# Schematic_STM32.net
KiCad netlist of a schematic drawn in Altium Designer
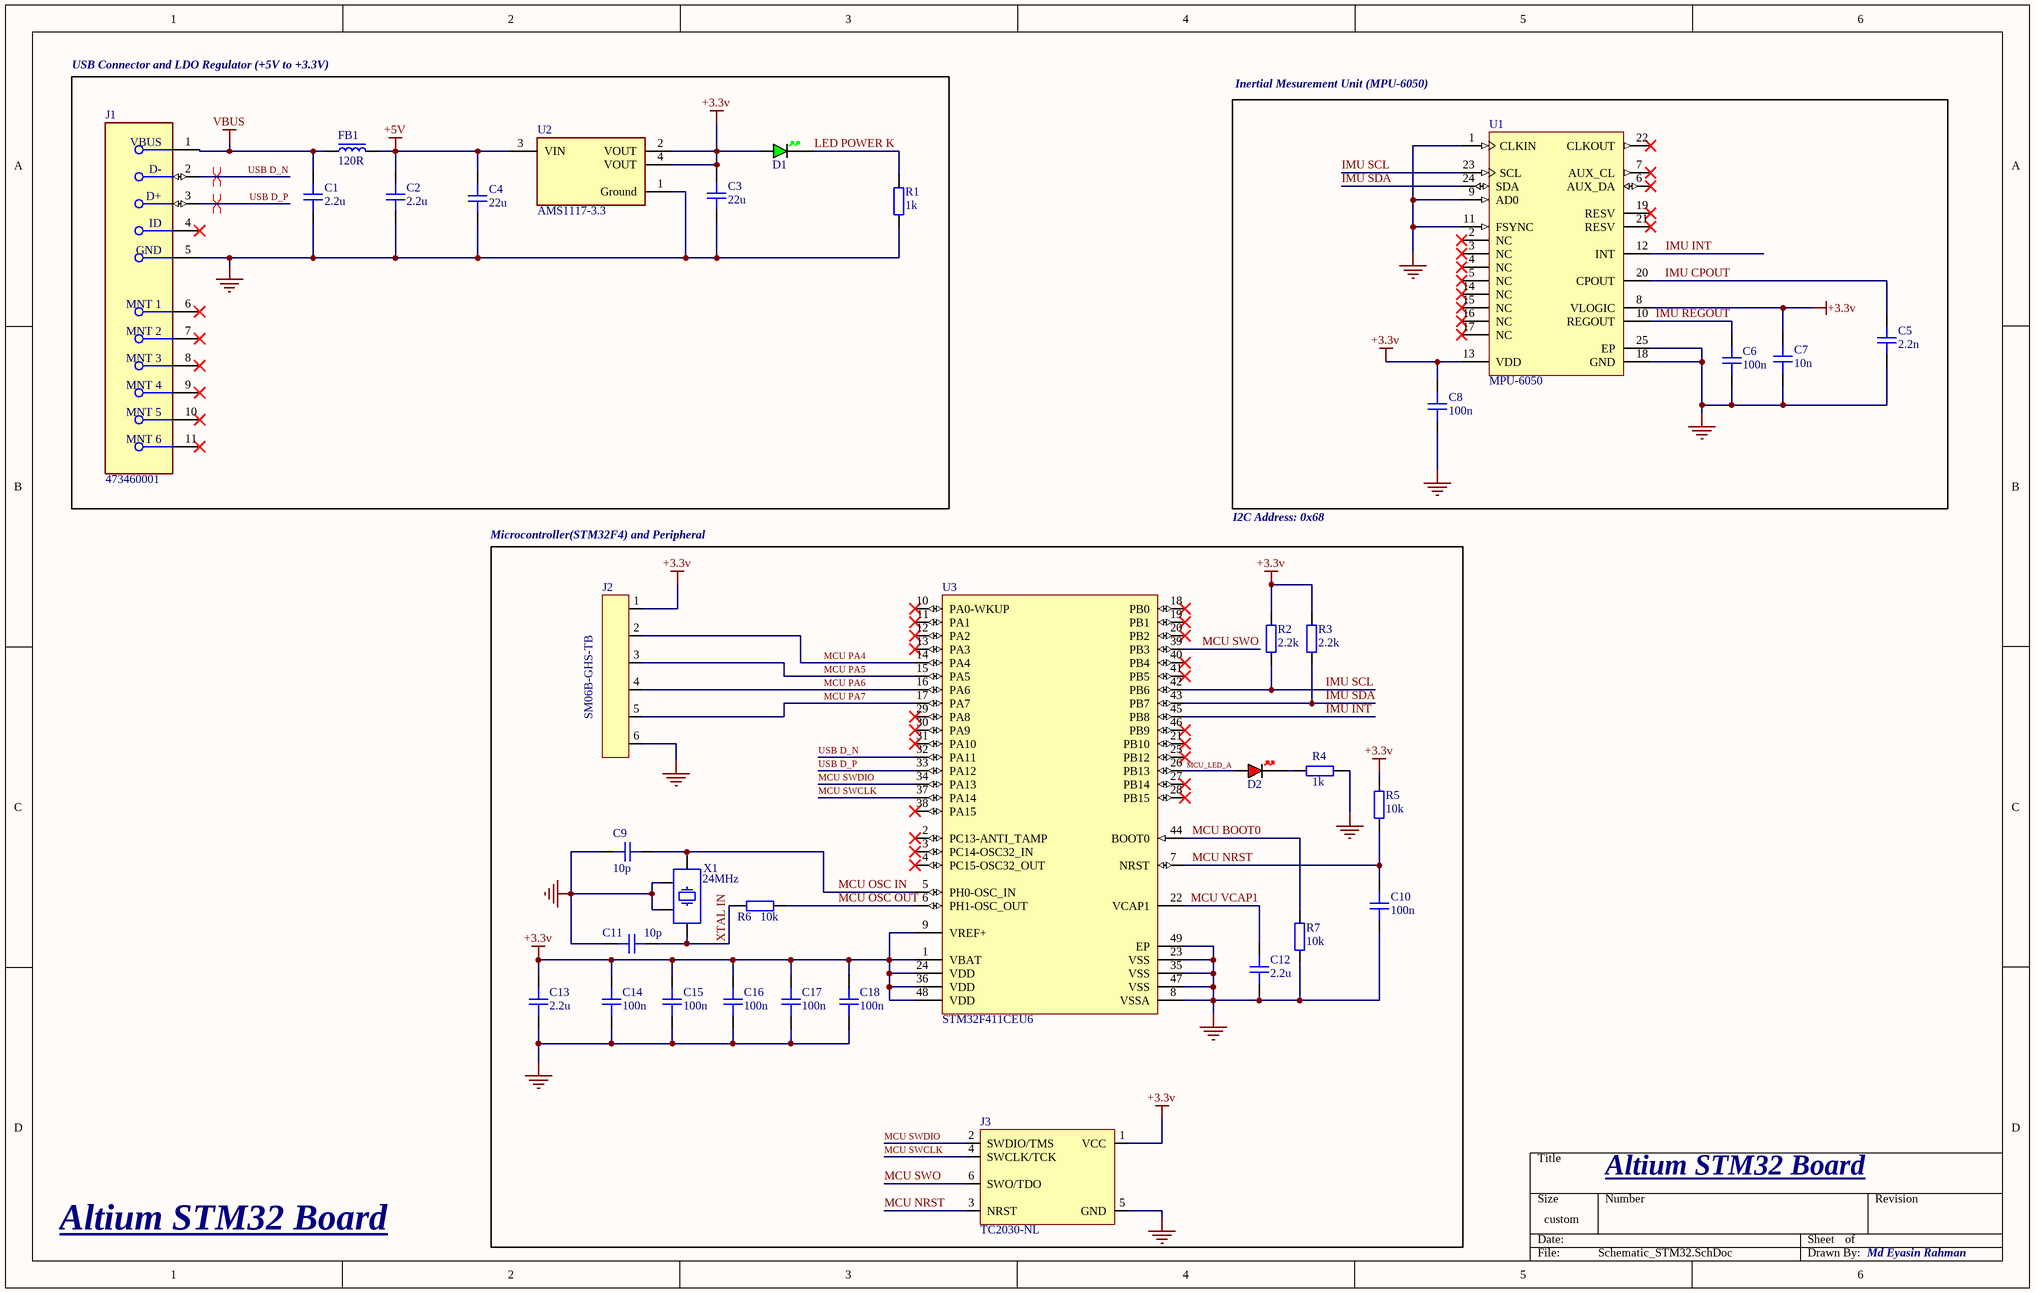
[diagram p0: Schematic_STM32.SchDoc]

(export (version "E")
  (design (tool "Eeschema 10.0.6"))
  (components
    (comp (ref "C1")
      (value "2.2u")
      (footprint "CAP_0603")
      (description "Capacitor SMD 0603")
      (libsource (lib "Schematic-Lib-PhilsLab") (part "CAP_0603"))
    )
    (comp (ref "C2")
      (value "2.2u")
      (footprint "CAP_0603")
      (description "Capacitor SMD 0603")
      (libsource (lib "Schematic-Lib-PhilsLab") (part "CAP_0603"))
    )
    (comp (ref "C3")
      (value "22u")
      (footprint "CAP_0805")
      (description "Capacitor SMD 0805")
      (libsource (lib "Schematic-Lib-PhilsLab") (part "CAP_0805"))
    )
    (comp (ref "C4")
      (value "22u")
      (footprint "CAP_0805")
      (description "Capacitor SMD 0805")
      (libsource (lib "Schematic-Lib-PhilsLab") (part "CAP_0805"))
    )
    (comp (ref "C5")
      (value "2.2n")
      (footprint "CAP_0402")
      (description "Capacitor SMD 0402")
      (libsource (lib "Schematic-Lib-PhilsLab") (part "CAP_0402"))
    )
    (comp (ref "C6")
      (value "100n")
      (footprint "CAP_0402")
      (description "Capacitor SMD 0402")
      (libsource (lib "Schematic-Lib-PhilsLab") (part "CAP_0402"))
    )
    (comp (ref "C7")
      (value "10n")
      (footprint "CAP_0402")
      (description "Capacitor SMD 0402")
      (libsource (lib "Schematic-Lib-PhilsLab") (part "CAP_0402"))
    )
    (comp (ref "C8")
      (value "100n")
      (footprint "CAP_0402")
      (description "Capacitor SMD 0402")
      (libsource (lib "Schematic-Lib-PhilsLab") (part "CAP_0402"))
    )
    (comp (ref "C9")
      (value "10p")
      (footprint "CAP_0402")
      (description "Capacitor SMD 0402")
      (libsource (lib "Schematic-Lib-PhilsLab") (part "CAP_0402"))
    )
    (comp (ref "C10")
      (value "100n")
      (footprint "CAP_0402")
      (description "Capacitor SMD 0402")
      (libsource (lib "Schematic-Lib-PhilsLab") (part "CAP_0402"))
    )
    (comp (ref "C11")
      (value "10p")
      (footprint "CAP_0402")
      (description "Capacitor SMD 0402")
      (libsource (lib "Schematic-Lib-PhilsLab") (part "CAP_0402"))
    )
    (comp (ref "C12")
      (value "2.2u")
      (footprint "CAP_0603")
      (description "Capacitor SMD 0603")
      (libsource (lib "Schematic-Lib-PhilsLab") (part "CAP_0603"))
    )
    (comp (ref "C13")
      (value "2.2u")
      (footprint "CAP_0603")
      (description "Capacitor SMD 0603")
      (libsource (lib "Schematic-Lib-PhilsLab") (part "CAP_0603"))
    )
    (comp (ref "C14")
      (value "100n")
      (footprint "CAP_0402")
      (description "Capacitor SMD 0402")
      (libsource (lib "Schematic-Lib-PhilsLab") (part "CAP_0402"))
    )
    (comp (ref "C15")
      (value "100n")
      (footprint "CAP_0402")
      (description "Capacitor SMD 0402")
      (libsource (lib "Schematic-Lib-PhilsLab") (part "CAP_0402"))
    )
    (comp (ref "C16")
      (value "100n")
      (footprint "CAP_0402")
      (description "Capacitor SMD 0402")
      (libsource (lib "Schematic-Lib-PhilsLab") (part "CAP_0402"))
    )
    (comp (ref "C17")
      (value "100n")
      (footprint "CAP_0402")
      (description "Capacitor SMD 0402")
      (libsource (lib "Schematic-Lib-PhilsLab") (part "CAP_0402"))
    )
    (comp (ref "C18")
      (value "100n")
      (footprint "CAP_0402")
      (description "Capacitor SMD 0402")
      (libsource (lib "Schematic-Lib-PhilsLab") (part "CAP_0402"))
    )
    (comp (ref "D1")
      (value "GREEN")
      (footprint "LED_0402_GREEN")
      (description "LED 0402 GREEN SMD")
      (libsource (lib "Schematic-Lib-PhilsLab") (part "LED_0402_GREEN"))
    )
    (comp (ref "D2")
      (value "RED")
      (footprint "LED_0402_RED")
      (description "LED 0402 RED SMD")
      (libsource (lib "Schematic-Lib-PhilsLab") (part "LED_0402_RED"))
    )
    (comp (ref "FB1")
      (value "120R")
      (footprint "FB_0603")
      (description "Ferrite Bead SMD 0603")
      (libsource (lib "Schematic-Lib-PhilsLab") (part "FB_0603"))
    )
    (comp (ref "J1")
      (value "473460001")
      (footprint "FP-473460001-MFG")
      (description "CONN RCPT USB2.0 MICRO B SMD R/A")
      (fields
        (field (name "OCTOPART") "https://octopart.com/47346-0001-molex-7164928")
        (field (name "MANUFACTURER") "Molex")
      )
      (libsource (lib "Altium Content Vault") (part "53ae1f1d9b557310b43ca686e5bb76a"))
    )
    (comp (ref "J2")
      (value "SM06B-GHS-TB")
      (footprint "SM06B-GHS-TB")
      (description "Header Connector 6 Position 1.25MM Pitch SMD Horizontal JST GH")
      (fields (field (name "MANUFACTURER") "JST"))
      (libsource (lib "Schematic-Lib-PhilsLab") (part "SM06B-GHS-TB"))
    )
    (comp (ref "J3")
      (value "TC2030-NL")
      (footprint "TC2030-NL-FP")
      (description "Tag-Connect No-Solder SWD Debug Connector (No Legs) DO NOT PLACE")
      (fields
        (field (name "MANUFACTURER") "Tag-Connect")
        (field (name "MANUFACTURER PART NUMBER") "TC2030-NL-FP")
      )
      (libsource (lib "Schematic-Lib-PhilsLab") (part "TC2030-NL"))
    )
    (comp (ref "R1")
      (value "1k")
      (footprint "RES_0402")
      (description "Resistor SMD 0402")
      (libsource (lib "Schematic-Lib-PhilsLab") (part "RES_0402"))
    )
    (comp (ref "R2")
      (value "2.2k")
      (footprint "RES_0402")
      (description "Resistor SMD 0402")
      (libsource (lib "Schematic-Lib-PhilsLab") (part "RES_0402"))
    )
    (comp (ref "R3")
      (value "2.2k")
      (footprint "RES_0402")
      (description "Resistor SMD 0402")
      (libsource (lib "Schematic-Lib-PhilsLab") (part "RES_0402"))
    )
    (comp (ref "R4")
      (value "1k")
      (footprint "RES_0402")
      (description "Resistor SMD 0402")
      (libsource (lib "Schematic-Lib-PhilsLab") (part "RES_0402"))
    )
    (comp (ref "R5")
      (value "10k")
      (footprint "RES_0402")
      (description "Resistor SMD 0402")
      (libsource (lib "Schematic-Lib-PhilsLab") (part "RES_0402"))
    )
    (comp (ref "R6")
      (value "10k")
      (footprint "RES_0402")
      (description "Resistor SMD 0402")
      (libsource (lib "Schematic-Lib-PhilsLab") (part "RES_0402"))
    )
    (comp (ref "R7")
      (value "10k")
      (footprint "RES_0402")
      (description "Resistor SMD 0402")
      (libsource (lib "Schematic-Lib-PhilsLab") (part "RES_0402"))
    )
    (comp (ref "U1")
      (value "MPU-6050")
      (footprint "IS-QFN-24_V")
      (fields (field (name "MANUFACTURER") "InvenSense"))
      (libsource (lib "Altium Content Vault") (part "IS-MPU-6050-QFN-24"))
    )
    (comp (ref "U2")
      (value "AMS1117-3.3")
      (footprint "FP-AMS1117-IPC_C")
      (description "LDO Voltage Regulators 1A, 3.3V")
      (fields
        (field (name "OCTOPART") "https://octopart.com/ams1117-3.3-advanced+monolithic+systems-25899300")
        (field (name "MANUFACTURER") "Advanced Monolithic Systems")
      )
      (libsource (lib "Altium Content Vault") (part "8bdbb5f8e77002000e30dd2845d0354"))
    )
    (comp (ref "U3")
      (value "STM32F411CEU6")
      (footprint "STM-UFQFPN48_L")
      (libsource (lib "Altium Content Vault") (part "MC-ARM-STM32F411-UFQFPN48"))
    )
    (comp (ref "X1")
      (value "24MHz")
      (footprint "XTAL_3225")
      (description "Crystal SMD 24MHz 10PPM 7pF 3225")
      (fields
        (field (name "MANUFACTURER") "Epson")
        (field (name "MANUFACTURER PART NUMBER") "TSX-3225 24.0000MF15X-AC")
      )
      (libsource (lib "Schematic-Lib-PhilsLab") (part "TSX-3225_24.0000MF15X-AC"))
    )
  )
  (nets
    (net (code "1") (name "+3.3v") (class "Default")
      (node (ref "C13") (pin "2") (pinfunction "2_2") (pintype "passive"))
      (node (ref "C14") (pin "2") (pinfunction "2_2") (pintype "passive"))
      (node (ref "C15") (pin "2") (pinfunction "2_2") (pintype "passive"))
      (node (ref "C16") (pin "2") (pinfunction "2_2") (pintype "passive"))
      (node (ref "C17") (pin "2") (pinfunction "2_2") (pintype "passive"))
      (node (ref "C18") (pin "2") (pinfunction "2_2") (pintype "passive"))
      (node (ref "C3") (pin "2") (pinfunction "2_2") (pintype "passive"))
      (node (ref "C7") (pin "2") (pinfunction "2_2") (pintype "passive"))
      (node (ref "C8") (pin "2") (pinfunction "2_2") (pintype "passive"))
      (node (ref "D1") (pin "A") (pinfunction "A_A") (pintype "passive"))
      (node (ref "J2") (pin "1") (pinfunction "1_1") (pintype "passive"))
      (node (ref "J3") (pin "1") (pinfunction "VCC_1") (pintype "passive"))
      (node (ref "R2") (pin "2") (pinfunction "2_2") (pintype "passive"))
      (node (ref "R3") (pin "2") (pinfunction "2_2") (pintype "passive"))
      (node (ref "R5") (pin "2") (pinfunction "2_2") (pintype "passive"))
      (node (ref "U1") (pin "13") (pinfunction "VDD_13") (pintype "power_in"))
      (node (ref "U1") (pin "8") (pinfunction "VLOGIC_8") (pintype "power_in"))
      (node (ref "U2") (pin "2") (pinfunction "VOUT_2") (pintype "passive"))
      (node (ref "U2") (pin "4") (pinfunction "VOUT_4") (pintype "passive"))
      (node (ref "U3") (pin "1") (pinfunction "VBAT_1") (pintype "power_in"))
      (node (ref "U3") (pin "24") (pinfunction "VDD_24") (pintype "power_in"))
      (node (ref "U3") (pin "36") (pinfunction "VDD_36") (pintype "power_in"))
      (node (ref "U3") (pin "48") (pinfunction "VDD_48") (pintype "power_in"))
      (node (ref "U3") (pin "9") (pinfunction "VREF+_9") (pintype "power_in"))
    )
    (net (code "2") (name "+5V") (class "Default")
      (node (ref "C2") (pin "2") (pinfunction "2_2") (pintype "passive"))
      (node (ref "C4") (pin "2") (pinfunction "2_2") (pintype "passive"))
      (node (ref "FB1") (pin "2") (pinfunction "2_2") (pintype "passive"))
      (node (ref "U2") (pin "3") (pinfunction "VIN_3") (pintype "power_in"))
    )
    (net (code "3") (name "/IMU CPOUT") (class "Default")
      (node (ref "C5") (pin "2") (pinfunction "2_2") (pintype "passive"))
      (node (ref "U1") (pin "20") (pinfunction "CPOUT_20") (pintype "passive"))
    )
    (net (code "4") (name "/IMU INT") (class "Default")
      (node (ref "U1") (pin "12") (pinfunction "INT_12") (pintype "open_collector"))
      (node (ref "U3") (pin "45") (pinfunction "PB8_45") (pintype "bidirectional"))
    )
    (net (code "5") (name "/IMU REGOUT") (class "Default")
      (node (ref "C6") (pin "2") (pinfunction "2_2") (pintype "passive"))
      (node (ref "U1") (pin "10") (pinfunction "REGOUT_10") (pintype "passive"))
    )
    (net (code "6") (name "/IMU SCL") (class "Default")
      (node (ref "R2") (pin "1") (pinfunction "1_1") (pintype "passive"))
      (node (ref "U1") (pin "23") (pinfunction "SCL_23") (pintype "input"))
      (node (ref "U3") (pin "42") (pinfunction "PB6_42") (pintype "bidirectional"))
    )
    (net (code "7") (name "/IMU SDA") (class "Default")
      (node (ref "R3") (pin "1") (pinfunction "1_1") (pintype "passive"))
      (node (ref "U1") (pin "24") (pinfunction "SDA_24") (pintype "bidirectional"))
      (node (ref "U3") (pin "43") (pinfunction "PB7_43") (pintype "bidirectional"))
    )
    (net (code "8") (name "/LED POWER K") (class "Default")
      (node (ref "D1") (pin "K") (pinfunction "K_K") (pintype "passive"))
      (node (ref "R1") (pin "2") (pinfunction "2_2") (pintype "passive"))
    )
    (net (code "9") (name "/MCU BOOT0") (class "Default")
      (node (ref "R7") (pin "2") (pinfunction "2_2") (pintype "passive"))
      (node (ref "U3") (pin "44") (pinfunction "BOOT0_44") (pintype "input"))
    )
    (net (code "10") (name "/MCU NRST") (class "Default")
      (node (ref "C10") (pin "2") (pinfunction "2_2") (pintype "passive"))
      (node (ref "J3") (pin "3") (pinfunction "NRST_3") (pintype "passive"))
      (node (ref "R5") (pin "1") (pinfunction "1_1") (pintype "passive"))
      (node (ref "U3") (pin "7") (pinfunction "NRST_7") (pintype "bidirectional"))
    )
    (net (code "11") (name "/MCU OSC IN") (class "Default")
      (node (ref "C9") (pin "2") (pinfunction "2_2") (pintype "passive"))
      (node (ref "U3") (pin "5") (pinfunction "PH0-OSC_IN_5") (pintype "bidirectional"))
      (node (ref "X1") (pin "1") (pinfunction "1_1") (pintype "passive"))
    )
    (net (code "12") (name "/MCU OSC OUT") (class "Default")
      (node (ref "R6") (pin "1") (pinfunction "1_1") (pintype "passive"))
      (node (ref "U3") (pin "6") (pinfunction "PH1-OSC_OUT_6") (pintype "bidirectional"))
    )
    (net (code "13") (name "/MCU PA4") (class "Default")
      (node (ref "J2") (pin "2") (pinfunction "2_2") (pintype "passive"))
      (node (ref "U3") (pin "14") (pinfunction "PA4_14") (pintype "bidirectional"))
    )
    (net (code "14") (name "/MCU PA5") (class "Default")
      (node (ref "J2") (pin "3") (pinfunction "3_3") (pintype "passive"))
      (node (ref "U3") (pin "15") (pinfunction "PA5_15") (pintype "bidirectional"))
    )
    (net (code "15") (name "/MCU PA6") (class "Default")
      (node (ref "J2") (pin "4") (pinfunction "4_4") (pintype "passive"))
      (node (ref "U3") (pin "16") (pinfunction "PA6_16") (pintype "bidirectional"))
    )
    (net (code "16") (name "/MCU PA7") (class "Default")
      (node (ref "J2") (pin "5") (pinfunction "5_5") (pintype "passive"))
      (node (ref "U3") (pin "17") (pinfunction "PA7_17") (pintype "bidirectional"))
    )
    (net (code "17") (name "/MCU SWCLK") (class "Default")
      (node (ref "J3") (pin "4") (pinfunction "SWCLK/TCK_4") (pintype "passive"))
      (node (ref "U3") (pin "37") (pinfunction "PA14_37") (pintype "bidirectional"))
    )
    (net (code "18") (name "/MCU SWDIO") (class "Default")
      (node (ref "J3") (pin "2") (pinfunction "SWDIO/TMS_2") (pintype "passive"))
      (node (ref "U3") (pin "34") (pinfunction "PA13_34") (pintype "bidirectional"))
    )
    (net (code "19") (name "/MCU SWO") (class "Default")
      (node (ref "J3") (pin "6") (pinfunction "SWO/TDO_6") (pintype "passive"))
      (node (ref "U3") (pin "39") (pinfunction "PB3_39") (pintype "bidirectional"))
    )
    (net (code "20") (name "/MCU VCAP1") (class "Default")
      (node (ref "C12") (pin "2") (pinfunction "2_2") (pintype "passive"))
      (node (ref "U3") (pin "22") (pinfunction "VCAP1_22") (pintype "passive"))
    )
    (net (code "21") (name "/MCU_LED_A") (class "Default")
      (node (ref "D2") (pin "A") (pinfunction "A_A") (pintype "passive"))
      (node (ref "U3") (pin "26") (pinfunction "PB13_26") (pintype "bidirectional"))
    )
    (net (code "22") (name "/USB D_N") (class "Default")
      (node (ref "J1") (pin "2") (pinfunction "D-_2") (pintype "bidirectional"))
      (node (ref "U3") (pin "32") (pinfunction "PA11_32") (pintype "bidirectional"))
    )
    (net (code "23") (name "/USB D_P") (class "Default")
      (node (ref "J1") (pin "3") (pinfunction "D+_3") (pintype "bidirectional"))
      (node (ref "U3") (pin "33") (pinfunction "PA12_33") (pintype "bidirectional"))
    )
    (net (code "24") (name "/XTAL IN") (class "Default")
      (node (ref "C11") (pin "2") (pinfunction "2_2") (pintype "passive"))
      (node (ref "R6") (pin "2") (pinfunction "2_2") (pintype "passive"))
      (node (ref "X1") (pin "3") (pinfunction "3_3") (pintype "passive"))
    )
    (net (code "25") (name "GND") (class "Default")
      (node (ref "C1") (pin "1") (pinfunction "1_1") (pintype "passive"))
      (node (ref "C10") (pin "1") (pinfunction "1_1") (pintype "passive"))
      (node (ref "C11") (pin "1") (pinfunction "1_1") (pintype "passive"))
      (node (ref "C12") (pin "1") (pinfunction "1_1") (pintype "passive"))
      (node (ref "C13") (pin "1") (pinfunction "1_1") (pintype "passive"))
      (node (ref "C14") (pin "1") (pinfunction "1_1") (pintype "passive"))
      (node (ref "C15") (pin "1") (pinfunction "1_1") (pintype "passive"))
      (node (ref "C16") (pin "1") (pinfunction "1_1") (pintype "passive"))
      (node (ref "C17") (pin "1") (pinfunction "1_1") (pintype "passive"))
      (node (ref "C18") (pin "1") (pinfunction "1_1") (pintype "passive"))
      (node (ref "C2") (pin "1") (pinfunction "1_1") (pintype "passive"))
      (node (ref "C3") (pin "1") (pinfunction "1_1") (pintype "passive"))
      (node (ref "C4") (pin "1") (pinfunction "1_1") (pintype "passive"))
      (node (ref "C5") (pin "1") (pinfunction "1_1") (pintype "passive"))
      (node (ref "C6") (pin "1") (pinfunction "1_1") (pintype "passive"))
      (node (ref "C7") (pin "1") (pinfunction "1_1") (pintype "passive"))
      (node (ref "C8") (pin "1") (pinfunction "1_1") (pintype "passive"))
      (node (ref "C9") (pin "1") (pinfunction "1_1") (pintype "passive"))
      (node (ref "J1") (pin "5") (pinfunction "GND_5") (pintype "power_in"))
      (node (ref "J2") (pin "6") (pinfunction "6_6") (pintype "passive"))
      (node (ref "J3") (pin "5") (pinfunction "GND_5") (pintype "passive"))
      (node (ref "R1") (pin "1") (pinfunction "1_1") (pintype "passive"))
      (node (ref "R4") (pin "1") (pinfunction "1_1") (pintype "passive"))
      (node (ref "R7") (pin "1") (pinfunction "1_1") (pintype "passive"))
      (node (ref "U1") (pin "1") (pinfunction "CLKIN_1") (pintype "input"))
      (node (ref "U1") (pin "11") (pinfunction "FSYNC_11") (pintype "input"))
      (node (ref "U1") (pin "18") (pinfunction "GND_18") (pintype "power_in"))
      (node (ref "U1") (pin "25") (pinfunction "EP_25") (pintype "power_in"))
      (node (ref "U1") (pin "9") (pinfunction "AD0_9") (pintype "input"))
      (node (ref "U2") (pin "1") (pinfunction "Ground_1") (pintype "power_in"))
      (node (ref "U3") (pin "23") (pinfunction "VSS_23") (pintype "power_in"))
      (node (ref "U3") (pin "35") (pinfunction "VSS_35") (pintype "power_in"))
      (node (ref "U3") (pin "47") (pinfunction "VSS_47") (pintype "power_in"))
      (node (ref "U3") (pin "49") (pinfunction "EP_49") (pintype "power_in"))
      (node (ref "U3") (pin "8") (pinfunction "VSSA_8") (pintype "power_in"))
      (node (ref "X1") (pin "2") (pinfunction "2_2") (pintype "passive"))
      (node (ref "X1") (pin "4") (pinfunction "4_4") (pintype "passive"))
    )
    (net (code "26") (name "Net-(D2-PadK)") (class "Default")
      (node (ref "D2") (pin "K") (pinfunction "K_K") (pintype "passive"))
      (node (ref "R4") (pin "2") (pinfunction "2_2") (pintype "passive"))
    )
    (net (code "27") (name "VBUS") (class "Default")
      (node (ref "C1") (pin "2") (pinfunction "2_2") (pintype "passive"))
      (node (ref "FB1") (pin "1") (pinfunction "1_1") (pintype "passive"))
      (node (ref "J1") (pin "1") (pinfunction "VBUS_1") (pintype "power_in"))
    )
    (net (code "28") (name "unconnected-(J1-ID-Pad4)") (class "Default")
      (node (ref "J1") (pin "4") (pinfunction "ID_4") (pintype "passive+no_connect"))
    )
    (net (code "29") (name "unconnected-(J1-MNT_1-Pad6)") (class "Default")
      (node (ref "J1") (pin "6") (pinfunction "MNT_1_6") (pintype "passive+no_connect"))
    )
    (net (code "30") (name "unconnected-(J1-MNT_2-Pad7)") (class "Default")
      (node (ref "J1") (pin "7") (pinfunction "MNT_2_7") (pintype "passive+no_connect"))
    )
    (net (code "31") (name "unconnected-(J1-MNT_3-Pad8)") (class "Default")
      (node (ref "J1") (pin "8") (pinfunction "MNT_3_8") (pintype "passive+no_connect"))
    )
    (net (code "32") (name "unconnected-(J1-MNT_4-Pad9)") (class "Default")
      (node (ref "J1") (pin "9") (pinfunction "MNT_4_9") (pintype "passive+no_connect"))
    )
    (net (code "33") (name "unconnected-(J1-MNT_5-Pad10)") (class "Default")
      (node (ref "J1") (pin "10") (pinfunction "MNT_5_10") (pintype "passive+no_connect"))
    )
    (net (code "34") (name "unconnected-(J1-MNT_6-Pad11)") (class "Default")
      (node (ref "J1") (pin "11") (pinfunction "MNT_6_11") (pintype "passive+no_connect"))
    )
    (net (code "35") (name "unconnected-(U1-AUX_CL-Pad7)") (class "Default")
      (node (ref "U1") (pin "7") (pinfunction "AUX_CL_7") (pintype "output+no_connect"))
    )
    (net (code "36") (name "unconnected-(U1-AUX_DA-Pad6)") (class "Default")
      (node (ref "U1") (pin "6") (pinfunction "AUX_DA_6") (pintype "bidirectional+no_connect"))
    )
    (net (code "37") (name "unconnected-(U1-CLKOUT-Pad22)") (class "Default")
      (node (ref "U1") (pin "22") (pinfunction "CLKOUT_22") (pintype "output+no_connect"))
    )
    (net (code "38") (name "unconnected-(U1-NC-Pad2)") (class "Default")
      (node (ref "U1") (pin "2") (pinfunction "NC_2") (pintype "passive+no_connect"))
    )
    (net (code "39") (name "unconnected-(U1-NC-Pad3)") (class "Default")
      (node (ref "U1") (pin "3") (pinfunction "NC_3") (pintype "passive+no_connect"))
    )
    (net (code "40") (name "unconnected-(U1-NC-Pad4)") (class "Default")
      (node (ref "U1") (pin "4") (pinfunction "NC_4") (pintype "passive+no_connect"))
    )
    (net (code "41") (name "unconnected-(U1-NC-Pad5)") (class "Default")
      (node (ref "U1") (pin "5") (pinfunction "NC_5") (pintype "passive+no_connect"))
    )
    (net (code "42") (name "unconnected-(U1-NC-Pad14)") (class "Default")
      (node (ref "U1") (pin "14") (pinfunction "NC_14") (pintype "passive+no_connect"))
    )
    (net (code "43") (name "unconnected-(U1-NC-Pad15)") (class "Default")
      (node (ref "U1") (pin "15") (pinfunction "NC_15") (pintype "passive+no_connect"))
    )
    (net (code "44") (name "unconnected-(U1-NC-Pad16)") (class "Default")
      (node (ref "U1") (pin "16") (pinfunction "NC_16") (pintype "passive+no_connect"))
    )
    (net (code "45") (name "unconnected-(U1-NC-Pad17)") (class "Default")
      (node (ref "U1") (pin "17") (pinfunction "NC_17") (pintype "passive+no_connect"))
    )
    (net (code "46") (name "unconnected-(U1-RESV-Pad19)") (class "Default")
      (node (ref "U1") (pin "19") (pinfunction "RESV_19") (pintype "passive+no_connect"))
    )
    (net (code "47") (name "unconnected-(U1-RESV-Pad21)") (class "Default")
      (node (ref "U1") (pin "21") (pinfunction "RESV_21") (pintype "passive+no_connect"))
    )
    (net (code "48") (name "unconnected-(U3-PA0-WKUP-Pad10)") (class "Default")
      (node (ref "U3") (pin "10") (pinfunction "PA0-WKUP_10") (pintype "bidirectional+no_connect"))
    )
    (net (code "49") (name "unconnected-(U3-PA1-Pad11)") (class "Default")
      (node (ref "U3") (pin "11") (pinfunction "PA1_11") (pintype "bidirectional+no_connect"))
    )
    (net (code "50") (name "unconnected-(U3-PA2-Pad12)") (class "Default")
      (node (ref "U3") (pin "12") (pinfunction "PA2_12") (pintype "bidirectional+no_connect"))
    )
    (net (code "51") (name "unconnected-(U3-PA3-Pad13)") (class "Default")
      (node (ref "U3") (pin "13") (pinfunction "PA3_13") (pintype "bidirectional+no_connect"))
    )
    (net (code "52") (name "unconnected-(U3-PA8-Pad29)") (class "Default")
      (node (ref "U3") (pin "29") (pinfunction "PA8_29") (pintype "bidirectional+no_connect"))
    )
    (net (code "53") (name "unconnected-(U3-PA9-Pad30)") (class "Default")
      (node (ref "U3") (pin "30") (pinfunction "PA9_30") (pintype "bidirectional+no_connect"))
    )
    (net (code "54") (name "unconnected-(U3-PA10-Pad31)") (class "Default")
      (node (ref "U3") (pin "31") (pinfunction "PA10_31") (pintype "bidirectional+no_connect"))
    )
    (net (code "55") (name "unconnected-(U3-PA15-Pad38)") (class "Default")
      (node (ref "U3") (pin "38") (pinfunction "PA15_38") (pintype "bidirectional+no_connect"))
    )
    (net (code "56") (name "unconnected-(U3-PB0-Pad18)") (class "Default")
      (node (ref "U3") (pin "18") (pinfunction "PB0_18") (pintype "bidirectional+no_connect"))
    )
    (net (code "57") (name "unconnected-(U3-PB1-Pad19)") (class "Default")
      (node (ref "U3") (pin "19") (pinfunction "PB1_19") (pintype "bidirectional+no_connect"))
    )
    (net (code "58") (name "unconnected-(U3-PB2-Pad20)") (class "Default")
      (node (ref "U3") (pin "20") (pinfunction "PB2_20") (pintype "bidirectional+no_connect"))
    )
    (net (code "59") (name "unconnected-(U3-PB4-Pad40)") (class "Default")
      (node (ref "U3") (pin "40") (pinfunction "PB4_40") (pintype "bidirectional+no_connect"))
    )
    (net (code "60") (name "unconnected-(U3-PB5-Pad41)") (class "Default")
      (node (ref "U3") (pin "41") (pinfunction "PB5_41") (pintype "bidirectional+no_connect"))
    )
    (net (code "61") (name "unconnected-(U3-PB9-Pad46)") (class "Default")
      (node (ref "U3") (pin "46") (pinfunction "PB9_46") (pintype "bidirectional+no_connect"))
    )
    (net (code "62") (name "unconnected-(U3-PB10-Pad21)") (class "Default")
      (node (ref "U3") (pin "21") (pinfunction "PB10_21") (pintype "bidirectional+no_connect"))
    )
    (net (code "63") (name "unconnected-(U3-PB12-Pad25)") (class "Default")
      (node (ref "U3") (pin "25") (pinfunction "PB12_25") (pintype "bidirectional+no_connect"))
    )
    (net (code "64") (name "unconnected-(U3-PB14-Pad27)") (class "Default")
      (node (ref "U3") (pin "27") (pinfunction "PB14_27") (pintype "bidirectional+no_connect"))
    )
    (net (code "65") (name "unconnected-(U3-PB15-Pad28)") (class "Default")
      (node (ref "U3") (pin "28") (pinfunction "PB15_28") (pintype "bidirectional+no_connect"))
    )
    (net (code "66") (name "unconnected-(U3-PC13-ANTI_TAMP-Pad2)") (class "Default")
      (node (ref "U3") (pin "2") (pinfunction "PC13-ANTI_TAMP_2") (pintype "bidirectional+no_connect"))
    )
    (net (code "67") (name "unconnected-(U3-PC14-OSC32_IN-Pad3)") (class "Default")
      (node (ref "U3") (pin "3") (pinfunction "PC14-OSC32_IN_3") (pintype "bidirectional+no_connect"))
    )
    (net (code "68") (name "unconnected-(U3-PC15-OSC32_OUT-Pad4)") (class "Default")
      (node (ref "U3") (pin "4") (pinfunction "PC15-OSC32_OUT_4") (pintype "bidirectional+no_connect"))
    )
  )
)
